# megashield_rs485.net
KiCad netlist of a schematic drawn in EAGLE
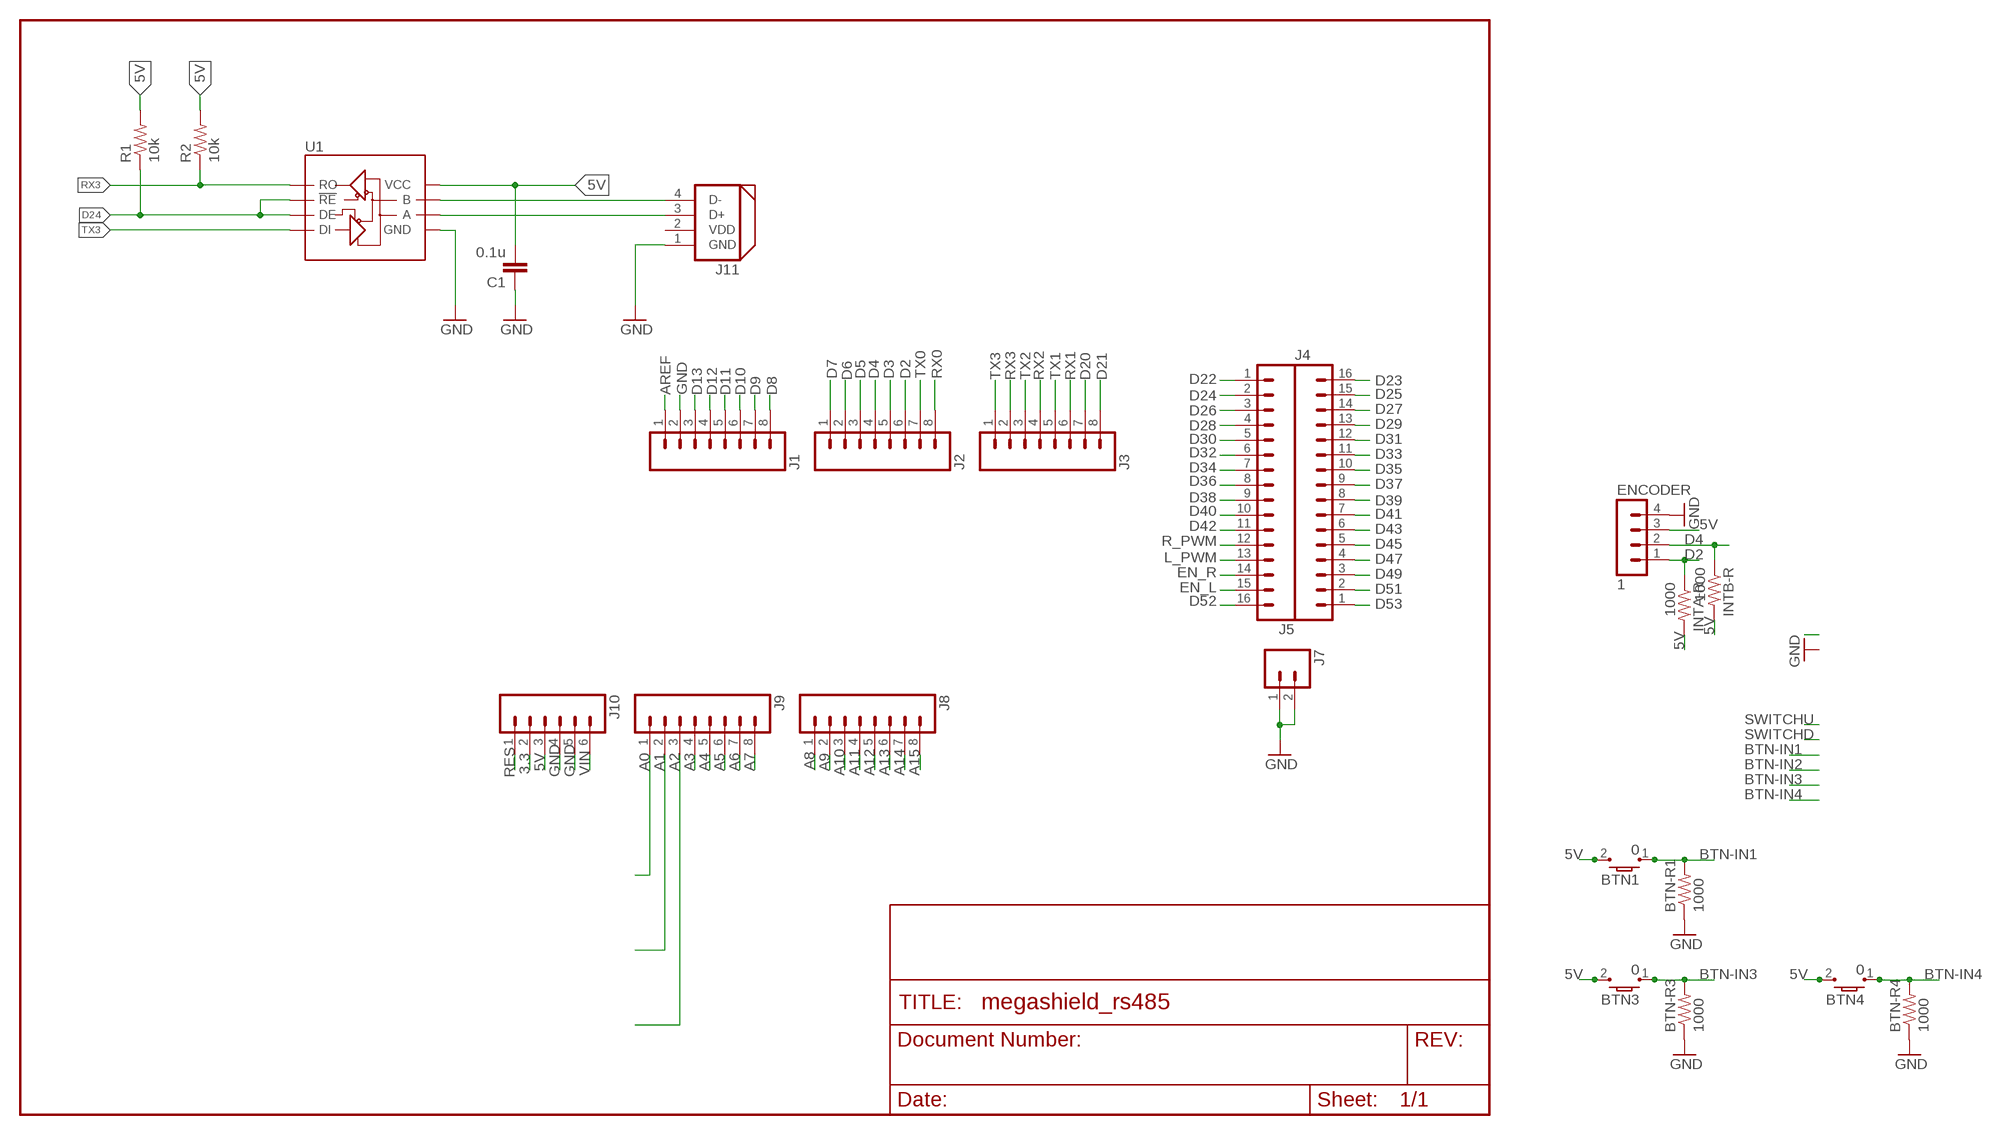
[diagram p0: schematic, sheet 1, part 1 of 2]
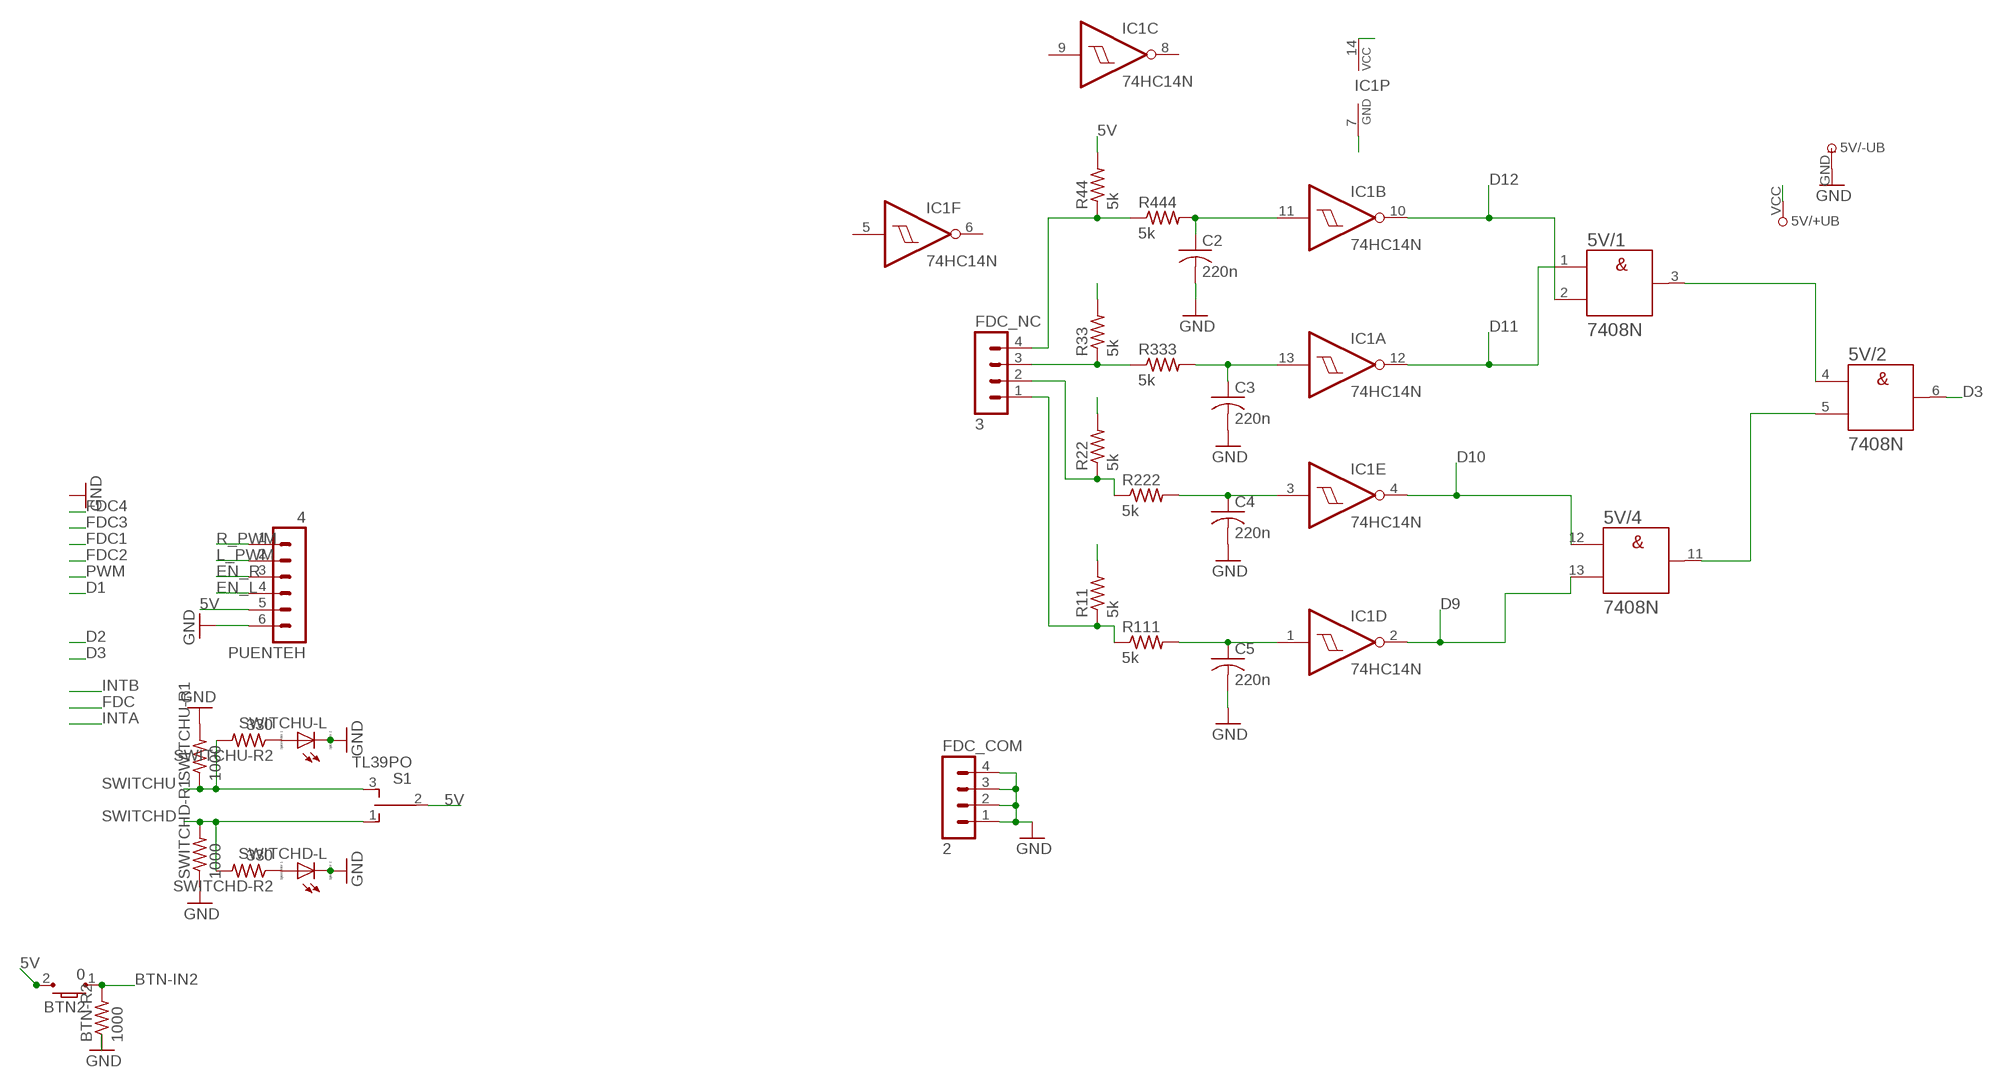
[diagram p1: schematic, sheet 1, part 2 of 2]

(export (version "E")
  (design (tool "Eeschema 10.0.6"))
  (components
    (comp (ref "5V")
      (value "7408N")
      (footprint "eagle-import:DIL14")
      (libsource (lib "eagle-import") (part "7408N"))
    )
    (comp (ref "BTN-R1")
      (value "1000")
      (footprint "eagle-import:0204_7")
      (libsource (lib "eagle-import") (part "resistor_R-US_0204/7"))
    )
    (comp (ref "BTN-R2")
      (value "1000")
      (footprint "eagle-import:0204_7")
      (libsource (lib "eagle-import") (part "resistor_R-US_0204/7"))
    )
    (comp (ref "BTN-R3")
      (value "1000")
      (footprint "eagle-import:0204_7")
      (libsource (lib "eagle-import") (part "resistor_R-US_0204/7"))
    )
    (comp (ref "BTN-R4")
      (value "1000")
      (footprint "eagle-import:0204_7")
      (libsource (lib "eagle-import") (part "resistor_R-US_0204/7"))
    )
    (comp (ref "BTN1")
      (value "0")
      (footprint "eagle-import:TL3303_J")
      (libsource (lib "eagle-import") (part "TL3302-J"))
    )
    (comp (ref "BTN2")
      (value "0")
      (footprint "eagle-import:TL3303_J")
      (libsource (lib "eagle-import") (part "TL3302-J"))
    )
    (comp (ref "BTN3")
      (value "0")
      (footprint "eagle-import:TL3303_J")
      (libsource (lib "eagle-import") (part "TL3302-J"))
    )
    (comp (ref "BTN4")
      (value "0")
      (footprint "eagle-import:TL3303_J")
      (libsource (lib "eagle-import") (part "TL3302-J"))
    )
    (comp (ref "C1")
      (value "0.1u")
      (footprint "eagle-import:CAP-PTH-SMALL")
      (libsource (lib "eagle-import") (part "CAPPTH"))
    )
    (comp (ref "C2")
      (value "220n")
      (footprint "eagle-import:C025-030X050")
      (libsource (lib "eagle-import") (part "C-US025-030X050"))
    )
    (comp (ref "C3")
      (value "220n")
      (footprint "eagle-import:C025-030X050")
      (libsource (lib "eagle-import") (part "C-US025-030X050"))
    )
    (comp (ref "C4")
      (value "220n")
      (footprint "eagle-import:C025-030X050")
      (libsource (lib "eagle-import") (part "C-US025-030X050"))
    )
    (comp (ref "C5")
      (value "220n")
      (footprint "eagle-import:C025-030X050")
      (libsource (lib "eagle-import") (part "C-US025-030X050"))
    )
    (comp (ref "ENCODER")
      (value "1")
      (footprint "eagle-import:MA04-1")
      (libsource (lib "eagle-import") (part "MA04-1"))
    )
    (comp (ref "FDC_COM")
      (value "2")
      (footprint "eagle-import:MA04-1")
      (libsource (lib "eagle-import") (part "MA04-1"))
    )
    (comp (ref "FDC_NC")
      (value "3")
      (footprint "eagle-import:MA04-1")
      (libsource (lib "eagle-import") (part "MA04-1"))
    )
    (comp (ref "IC1")
      (value "74HC14N")
      (footprint "eagle-import:DIL14")
      (libsource (lib "eagle-import") (part "7414NHC"))
    )
    (comp (ref "INTA-R")
      (value "1000")
      (footprint "eagle-import:0204_7")
      (libsource (lib "eagle-import") (part "resistor_R-US_0204/7"))
    )
    (comp (ref "INTB-R")
      (value "1000")
      (footprint "eagle-import:0204_7")
      (libsource (lib "eagle-import") (part "resistor_R-US_0204/7"))
    )
    (comp (ref "J1")
      (value "M08LONGPADS")
      (footprint "eagle-import:1X08_LONGPADS")
      (libsource (lib "eagle-import") (part "M08LONGPADS"))
    )
    (comp (ref "J2")
      (value "M08LONGPADS")
      (footprint "eagle-import:1X08_LONGPADS")
      (libsource (lib "eagle-import") (part "M08LONGPADS"))
    )
    (comp (ref "J3")
      (value "M08LONGPADS")
      (footprint "eagle-import:1X08_LONGPADS")
      (libsource (lib "eagle-import") (part "M08LONGPADS"))
    )
    (comp (ref "J4")
      (value "M16PTH")
      (footprint "eagle-import:1X16")
      (libsource (lib "eagle-import") (part "M16PTH"))
    )
    (comp (ref "J5")
      (value "M16PTH")
      (footprint "eagle-import:1X16")
      (libsource (lib "eagle-import") (part "M16PTH"))
    )
    (comp (ref "J7")
      (value "M02PTH")
      (footprint "eagle-import:1X02")
      (libsource (lib "eagle-import") (part "M02PTH"))
    )
    (comp (ref "J8")
      (value "M08LONGPADS")
      (footprint "eagle-import:1X08_LONGPADS")
      (libsource (lib "eagle-import") (part "M08LONGPADS"))
    )
    (comp (ref "J9")
      (value "M08LONGPADS")
      (footprint "eagle-import:1X08_LONGPADS")
      (libsource (lib "eagle-import") (part "M08LONGPADS"))
    )
    (comp (ref "J10")
      (value "M06LONGPADS")
      (footprint "eagle-import:1X06_LONGPADS")
      (libsource (lib "eagle-import") (part "M06LONGPADS"))
    )
    (comp (ref "J11")
      (value "DYNAMIXEL_RS485")
      (footprint "eagle-import:DYNAMIXEL_SPOX_04")
      (libsource (lib "eagle-import") (part "DYNAMIXEL_RS485"))
    )
    (comp (ref "PUENTEH")
      (value "4")
      (footprint "eagle-import:MA06-1")
      (libsource (lib "eagle-import") (part "MA06-1"))
    )
    (comp (ref "R1")
      (value "10k")
      (footprint "eagle-import:AXIAL-0.4")
      (libsource (lib "eagle-import") (part "RESISTORPTH-1/4W"))
    )
    (comp (ref "R2")
      (value "10k")
      (footprint "eagle-import:AXIAL-0.4")
      (libsource (lib "eagle-import") (part "RESISTORPTH-1/4W"))
    )
    (comp (ref "R11")
      (value "5k")
      (footprint "eagle-import:0204_7")
      (libsource (lib "eagle-import") (part "R-US_0204/7"))
    )
    (comp (ref "R22")
      (value "5k")
      (footprint "eagle-import:0204_7")
      (libsource (lib "eagle-import") (part "R-US_0204/7"))
    )
    (comp (ref "R33")
      (value "5k")
      (footprint "eagle-import:0204_7")
      (libsource (lib "eagle-import") (part "R-US_0204/7"))
    )
    (comp (ref "R44")
      (value "5k")
      (footprint "eagle-import:0204_7")
      (libsource (lib "eagle-import") (part "R-US_0204/7"))
    )
    (comp (ref "R111")
      (value "5k")
      (footprint "eagle-import:0204_7")
      (libsource (lib "eagle-import") (part "R-US_0204/7"))
    )
    (comp (ref "R222")
      (value "5k")
      (footprint "eagle-import:0204_7")
      (libsource (lib "eagle-import") (part "R-US_0204/7"))
    )
    (comp (ref "R333")
      (value "5k")
      (footprint "eagle-import:0204_7")
      (libsource (lib "eagle-import") (part "R-US_0204/7"))
    )
    (comp (ref "R444")
      (value "5k")
      (footprint "eagle-import:0204_7")
      (libsource (lib "eagle-import") (part "R-US_0204/7"))
    )
    (comp (ref "S1")
      (value "TL39PO")
      (footprint "eagle-import:TL3XPO")
      (libsource (lib "eagle-import") (part "TL39PO"))
    )
    (comp (ref "SWITCHD-L")
      (value "LED_ELD260")
      (footprint "eagle-import:LED_LD260")
      (libsource (lib "eagle-import") (part "LED_ELD260"))
    )
    (comp (ref "SWITCHD-R1")
      (value "1000")
      (footprint "eagle-import:0204_7")
      (libsource (lib "eagle-import") (part "resistor_R-US_0204/7"))
    )
    (comp (ref "SWITCHD-R2")
      (value "330")
      (footprint "eagle-import:0204_7")
      (libsource (lib "eagle-import") (part "resistor_R-US_0204/7"))
    )
    (comp (ref "SWITCHU-L")
      (value "LED_ELD260")
      (footprint "eagle-import:LED_LD260")
      (libsource (lib "eagle-import") (part "LED_ELD260"))
    )
    (comp (ref "SWITCHU-R1")
      (value "1000")
      (footprint "eagle-import:0204_7")
      (libsource (lib "eagle-import") (part "resistor_R-US_0204/7"))
    )
    (comp (ref "SWITCHU-R2")
      (value "330")
      (footprint "eagle-import:0204_7")
      (libsource (lib "eagle-import") (part "resistor_R-US_0204/7"))
    )
    (comp (ref "U1")
      (value "RS485")
      (footprint "eagle-import:DIL08")
      (libsource (lib "eagle-import") (part "SN75176B"))
    )
  )
  (nets
    (net (code "1") (name "/3.3") (class "Default")
      (node (ref "J10") (pin "2") (pinfunction "2_2") (pintype "passive"))
    )
    (net (code "2") (name "/A0") (class "Default")
      (node (ref "J9") (pin "1") (pinfunction "1_1") (pintype "passive"))
    )
    (net (code "3") (name "/A1") (class "Default")
      (node (ref "J9") (pin "2") (pinfunction "2_2") (pintype "passive"))
    )
    (net (code "4") (name "/A2") (class "Default")
      (node (ref "J9") (pin "3") (pinfunction "3_3") (pintype "passive"))
    )
    (net (code "5") (name "/A3") (class "Default")
      (node (ref "J9") (pin "4") (pinfunction "4_4") (pintype "passive"))
    )
    (net (code "6") (name "/A4") (class "Default")
      (node (ref "J9") (pin "5") (pinfunction "5_5") (pintype "passive"))
    )
    (net (code "7") (name "/A5") (class "Default")
      (node (ref "J9") (pin "6") (pinfunction "6_6") (pintype "passive"))
    )
    (net (code "8") (name "/A6") (class "Default")
      (node (ref "J9") (pin "7") (pinfunction "7_7") (pintype "passive"))
    )
    (net (code "9") (name "/A7") (class "Default")
      (node (ref "J9") (pin "8") (pinfunction "8_8") (pintype "passive"))
    )
    (net (code "10") (name "/A8") (class "Default")
      (node (ref "J8") (pin "1") (pinfunction "1_1") (pintype "passive"))
    )
    (net (code "11") (name "/A9") (class "Default")
      (node (ref "J8") (pin "2") (pinfunction "2_2") (pintype "passive"))
    )
    (net (code "12") (name "/A10") (class "Default")
      (node (ref "J8") (pin "3") (pinfunction "3_3") (pintype "passive"))
    )
    (net (code "13") (name "/A11") (class "Default")
      (node (ref "J8") (pin "4") (pinfunction "4_4") (pintype "passive"))
    )
    (net (code "14") (name "/A12") (class "Default")
      (node (ref "J8") (pin "5") (pinfunction "5_5") (pintype "passive"))
    )
    (net (code "15") (name "/A13") (class "Default")
      (node (ref "J8") (pin "6") (pinfunction "6_6") (pintype "passive"))
    )
    (net (code "16") (name "/A14") (class "Default")
      (node (ref "J8") (pin "7") (pinfunction "7_7") (pintype "passive"))
    )
    (net (code "17") (name "/A15") (class "Default")
      (node (ref "J8") (pin "8") (pinfunction "8_8") (pintype "passive"))
    )
    (net (code "18") (name "/AREF") (class "Default")
      (node (ref "J1") (pin "1") (pinfunction "1_1") (pintype "passive"))
    )
    (net (code "19") (name "/BTN-IN1") (class "Default")
      (node (ref "BTN-R1") (pin "2") (pinfunction "2_2") (pintype "passive"))
      (node (ref "BTN1") (pin "1") (pinfunction "1_1") (pintype "passive"))
    )
    (net (code "20") (name "/BTN-IN2") (class "Default")
      (node (ref "BTN-R2") (pin "2") (pinfunction "2_2") (pintype "passive"))
      (node (ref "BTN2") (pin "1") (pinfunction "1_1") (pintype "passive"))
    )
    (net (code "21") (name "/BTN-IN3") (class "Default")
      (node (ref "BTN-R3") (pin "2") (pinfunction "2_2") (pintype "passive"))
      (node (ref "BTN3") (pin "1") (pinfunction "1_1") (pintype "passive"))
    )
    (net (code "22") (name "/BTN-IN4") (class "Default")
      (node (ref "BTN-R4") (pin "2") (pinfunction "2_2") (pintype "passive"))
      (node (ref "BTN4") (pin "1") (pinfunction "1_1") (pintype "passive"))
    )
    (net (code "24") (name "/D2") (class "Default")
      (node (ref "ENCODER") (pin "1") (pinfunction "1_1") (pintype "passive"))
      (node (ref "INTA-R") (pin "1") (pinfunction "1_1") (pintype "passive"))
      (node (ref "J2") (pin "6") (pinfunction "6_6") (pintype "passive"))
    )
    (net (code "25") (name "/D3") (class "Default")
      (node (ref "5V") (pin "6") (pinfunction "Y_6") (pintype "output"))
      (node (ref "J2") (pin "5") (pinfunction "5_5") (pintype "passive"))
    )
    (net (code "26") (name "/D4") (class "Default")
      (node (ref "ENCODER") (pin "2") (pinfunction "2_2") (pintype "passive"))
      (node (ref "INTB-R") (pin "1") (pinfunction "1_1") (pintype "passive"))
      (node (ref "J2") (pin "4") (pinfunction "4_4") (pintype "passive"))
    )
    (net (code "27") (name "/D5") (class "Default")
      (node (ref "J2") (pin "3") (pinfunction "3_3") (pintype "passive"))
    )
    (net (code "28") (name "/D6") (class "Default")
      (node (ref "J2") (pin "2") (pinfunction "2_2") (pintype "passive"))
    )
    (net (code "29") (name "/D7") (class "Default")
      (node (ref "J2") (pin "1") (pinfunction "1_1") (pintype "passive"))
    )
    (net (code "30") (name "/D8") (class "Default")
      (node (ref "J1") (pin "8") (pinfunction "8_8") (pintype "passive"))
    )
    (net (code "31") (name "/D9") (class "Default")
      (node (ref "5V") (pin "13") (pinfunction "B_13") (pintype "input"))
      (node (ref "IC1") (pin "2") (pinfunction "O_2") (pintype "output"))
      (node (ref "J1") (pin "7") (pinfunction "7_7") (pintype "passive"))
    )
    (net (code "32") (name "/D10") (class "Default")
      (node (ref "5V") (pin "12") (pinfunction "A_12") (pintype "input"))
      (node (ref "IC1") (pin "4") (pinfunction "O_4") (pintype "output"))
      (node (ref "J1") (pin "6") (pinfunction "6_6") (pintype "passive"))
    )
    (net (code "33") (name "/D11") (class "Default")
      (node (ref "5V") (pin "1") (pinfunction "A_1") (pintype "input"))
      (node (ref "IC1") (pin "12") (pinfunction "O_12") (pintype "output"))
      (node (ref "J1") (pin "5") (pinfunction "5_5") (pintype "passive"))
    )
    (net (code "34") (name "/D12") (class "Default")
      (node (ref "5V") (pin "2") (pinfunction "B_2") (pintype "input"))
      (node (ref "IC1") (pin "10") (pinfunction "O_10") (pintype "output"))
      (node (ref "J1") (pin "4") (pinfunction "4_4") (pintype "passive"))
    )
    (net (code "35") (name "/D13") (class "Default")
      (node (ref "J1") (pin "3") (pinfunction "3_3") (pintype "passive"))
    )
    (net (code "36") (name "/D20") (class "Default")
      (node (ref "J3") (pin "7") (pinfunction "7_7") (pintype "passive"))
    )
    (net (code "37") (name "/D21") (class "Default")
      (node (ref "J3") (pin "8") (pinfunction "8_8") (pintype "passive"))
    )
    (net (code "38") (name "/D22") (class "Default")
      (node (ref "J5") (pin "1") (pinfunction "1_1") (pintype "passive"))
    )
    (net (code "39") (name "/D23") (class "Default")
      (node (ref "J4") (pin "16") (pinfunction "16_16") (pintype "passive"))
    )
    (net (code "40") (name "/D25") (class "Default")
      (node (ref "J4") (pin "15") (pinfunction "15_15") (pintype "passive"))
    )
    (net (code "41") (name "/D26") (class "Default")
      (node (ref "J5") (pin "3") (pinfunction "3_3") (pintype "passive"))
    )
    (net (code "42") (name "/D27") (class "Default")
      (node (ref "J4") (pin "14") (pinfunction "14_14") (pintype "passive"))
    )
    (net (code "43") (name "/D28") (class "Default")
      (node (ref "J5") (pin "4") (pinfunction "4_4") (pintype "passive"))
    )
    (net (code "44") (name "/D29") (class "Default")
      (node (ref "J4") (pin "13") (pinfunction "13_13") (pintype "passive"))
    )
    (net (code "45") (name "/D30") (class "Default")
      (node (ref "J5") (pin "5") (pinfunction "5_5") (pintype "passive"))
    )
    (net (code "46") (name "/D31") (class "Default")
      (node (ref "J4") (pin "12") (pinfunction "12_12") (pintype "passive"))
    )
    (net (code "47") (name "/D32") (class "Default")
      (node (ref "J5") (pin "6") (pinfunction "6_6") (pintype "passive"))
    )
    (net (code "48") (name "/D33") (class "Default")
      (node (ref "J4") (pin "11") (pinfunction "11_11") (pintype "passive"))
    )
    (net (code "49") (name "/D34") (class "Default")
      (node (ref "J5") (pin "7") (pinfunction "7_7") (pintype "passive"))
    )
    (net (code "50") (name "/D35") (class "Default")
      (node (ref "J4") (pin "10") (pinfunction "10_10") (pintype "passive"))
    )
    (net (code "51") (name "/D36") (class "Default")
      (node (ref "J5") (pin "8") (pinfunction "8_8") (pintype "passive"))
    )
    (net (code "52") (name "/D37") (class "Default")
      (node (ref "J4") (pin "9") (pinfunction "9_9") (pintype "passive"))
    )
    (net (code "53") (name "/D38") (class "Default")
      (node (ref "J5") (pin "9") (pinfunction "9_9") (pintype "passive"))
    )
    (net (code "54") (name "/D39") (class "Default")
      (node (ref "J4") (pin "8") (pinfunction "8_8") (pintype "passive"))
    )
    (net (code "55") (name "/D40") (class "Default")
      (node (ref "J5") (pin "10") (pinfunction "10_10") (pintype "passive"))
    )
    (net (code "56") (name "/D41") (class "Default")
      (node (ref "J4") (pin "7") (pinfunction "7_7") (pintype "passive"))
    )
    (net (code "57") (name "/D42") (class "Default")
      (node (ref "J5") (pin "11") (pinfunction "11_11") (pintype "passive"))
    )
    (net (code "58") (name "/D43") (class "Default")
      (node (ref "J4") (pin "6") (pinfunction "6_6") (pintype "passive"))
    )
    (net (code "59") (name "/D45") (class "Default")
      (node (ref "J4") (pin "5") (pinfunction "5_5") (pintype "passive"))
    )
    (net (code "60") (name "/D47") (class "Default")
      (node (ref "J4") (pin "4") (pinfunction "4_4") (pintype "passive"))
    )
    (net (code "61") (name "/D49") (class "Default")
      (node (ref "J4") (pin "3") (pinfunction "3_3") (pintype "passive"))
    )
    (net (code "62") (name "/D51") (class "Default")
      (node (ref "J4") (pin "2") (pinfunction "2_2") (pintype "passive"))
    )
    (net (code "63") (name "/D52") (class "Default")
      (node (ref "J5") (pin "16") (pinfunction "16_16") (pintype "passive"))
    )
    (net (code "64") (name "/D53") (class "Default")
      (node (ref "J4") (pin "1") (pinfunction "1_1") (pintype "passive"))
    )
    (net (code "65") (name "/EN_L") (class "Default")
      (node (ref "J5") (pin "15") (pinfunction "15_15") (pintype "passive"))
      (node (ref "PUENTEH") (pin "4") (pinfunction "4_4") (pintype "passive"))
    )
    (net (code "66") (name "/EN_R") (class "Default")
      (node (ref "J5") (pin "14") (pinfunction "14_14") (pintype "passive"))
      (node (ref "PUENTEH") (pin "3") (pinfunction "3_3") (pintype "passive"))
    )
    (net (code "74") (name "/L_PWM") (class "Default")
      (node (ref "J5") (pin "13") (pinfunction "13_13") (pintype "passive"))
      (node (ref "PUENTEH") (pin "2") (pinfunction "2_2") (pintype "passive"))
    )
    (net (code "76") (name "/RES") (class "Default")
      (node (ref "J10") (pin "1") (pinfunction "1_1") (pintype "passive"))
    )
    (net (code "77") (name "/RX0") (class "Default")
      (node (ref "J2") (pin "8") (pinfunction "8_8") (pintype "passive"))
    )
    (net (code "78") (name "/RX1") (class "Default")
      (node (ref "J3") (pin "6") (pinfunction "6_6") (pintype "passive"))
    )
    (net (code "79") (name "/RX2") (class "Default")
      (node (ref "J3") (pin "4") (pinfunction "4_4") (pintype "passive"))
    )
    (net (code "80") (name "/R_PWM") (class "Default")
      (node (ref "J5") (pin "12") (pinfunction "12_12") (pintype "passive"))
      (node (ref "PUENTEH") (pin "1") (pinfunction "1_1") (pintype "passive"))
    )
    (net (code "81") (name "/SWITCHD") (class "Default")
      (node (ref "S1") (pin "1") (pinfunction "O_1") (pintype "passive"))
      (node (ref "SWITCHD-R1") (pin "2") (pinfunction "2_2") (pintype "passive"))
      (node (ref "SWITCHD-R2") (pin "2") (pinfunction "2_2") (pintype "passive"))
    )
    (net (code "82") (name "/SWITCHU") (class "Default")
      (node (ref "S1") (pin "3") (pinfunction "S_3") (pintype "passive"))
      (node (ref "SWITCHU-R1") (pin "1") (pinfunction "1_1") (pintype "passive"))
      (node (ref "SWITCHU-R2") (pin "2") (pinfunction "2_2") (pintype "passive"))
    )
    (net (code "83") (name "/TX0") (class "Default")
      (node (ref "J2") (pin "7") (pinfunction "7_7") (pintype "passive"))
    )
    (net (code "84") (name "/TX1") (class "Default")
      (node (ref "J3") (pin "5") (pinfunction "5_5") (pintype "passive"))
    )
    (net (code "85") (name "/TX2") (class "Default")
      (node (ref "J3") (pin "3") (pinfunction "3_3") (pintype "passive"))
    )
    (net (code "86") (name "/VDD") (class "Default")
      (node (ref "J11") (pin "2") (pinfunction "VDD_2") (pintype "power_in"))
    )
    (net (code "87") (name "/VIN") (class "Default")
      (node (ref "J10") (pin "6") (pinfunction "6_6") (pintype "passive"))
    )
    (net (code "88") (name "5V") (class "Default")
      (node (ref "5V") (pin "VCC") (pinfunction "+UB_VCC") (pintype "power_in"))
      (node (ref "BTN1") (pin "2") (pinfunction "2_2") (pintype "passive"))
      (node (ref "BTN2") (pin "2") (pinfunction "2_2") (pintype "passive"))
      (node (ref "BTN3") (pin "2") (pinfunction "2_2") (pintype "passive"))
      (node (ref "BTN4") (pin "2") (pinfunction "2_2") (pintype "passive"))
      (node (ref "C1") (pin "2") (pinfunction "2_2") (pintype "passive"))
      (node (ref "ENCODER") (pin "3") (pinfunction "3_3") (pintype "passive"))
      (node (ref "IC1") (pin "14") (pinfunction "VCC_14") (pintype "power_in"))
      (node (ref "INTA-R") (pin "2") (pinfunction "2_2") (pintype "passive"))
      (node (ref "INTB-R") (pin "2") (pinfunction "2_2") (pintype "passive"))
      (node (ref "J10") (pin "3") (pinfunction "3_3") (pintype "passive"))
      (node (ref "PUENTEH") (pin "5") (pinfunction "5_5") (pintype "passive"))
      (node (ref "R1") (pin "P$2") (pinfunction "2_P$2") (pintype "passive"))
      (node (ref "R11") (pin "2") (pinfunction "2_2") (pintype "passive"))
      (node (ref "R2") (pin "P$2") (pinfunction "2_P$2") (pintype "passive"))
      (node (ref "R22") (pin "2") (pinfunction "2_2") (pintype "passive"))
      (node (ref "R33") (pin "2") (pinfunction "2_2") (pintype "passive"))
      (node (ref "R44") (pin "2") (pinfunction "2_2") (pintype "passive"))
      (node (ref "S1") (pin "2") (pinfunction "P_2") (pintype "passive"))
      (node (ref "U1") (pin "8") (pinfunction "VCC_8") (pintype "bidirectional"))
    )
    (net (code "89") (name "D24") (class "Default")
      (node (ref "J5") (pin "2") (pinfunction "2_2") (pintype "passive"))
      (node (ref "R1") (pin "P$1") (pinfunction "1_P$1") (pintype "passive"))
      (node (ref "U1") (pin "2") (pinfunction "~{RE}_2") (pintype "bidirectional"))
      (node (ref "U1") (pin "3") (pinfunction "DE_3") (pintype "bidirectional"))
    )
    (net (code "90") (name "GND") (class "Default")
      (node (ref "5V") (pin "GND") (pinfunction "-UB_GND") (pintype "power_in"))
      (node (ref "BTN-R1") (pin "1") (pinfunction "1_1") (pintype "passive"))
      (node (ref "BTN-R2") (pin "1") (pinfunction "1_1") (pintype "passive"))
      (node (ref "BTN-R3") (pin "1") (pinfunction "1_1") (pintype "passive"))
      (node (ref "BTN-R4") (pin "1") (pinfunction "1_1") (pintype "passive"))
      (node (ref "C1") (pin "1") (pinfunction "1_1") (pintype "passive"))
      (node (ref "C2") (pin "2") (pinfunction "2_2") (pintype "passive"))
      (node (ref "C3") (pin "2") (pinfunction "2_2") (pintype "passive"))
      (node (ref "C4") (pin "2") (pinfunction "2_2") (pintype "passive"))
      (node (ref "C5") (pin "2") (pinfunction "2_2") (pintype "passive"))
      (node (ref "ENCODER") (pin "4") (pinfunction "4_4") (pintype "passive"))
      (node (ref "FDC_COM") (pin "1") (pinfunction "1_1") (pintype "passive"))
      (node (ref "FDC_COM") (pin "2") (pinfunction "2_2") (pintype "passive"))
      (node (ref "FDC_COM") (pin "3") (pinfunction "3_3") (pintype "passive"))
      (node (ref "FDC_COM") (pin "4") (pinfunction "4_4") (pintype "passive"))
      (node (ref "IC1") (pin "7") (pinfunction "GND_7") (pintype "power_in"))
      (node (ref "J1") (pin "2") (pinfunction "2_2") (pintype "passive"))
      (node (ref "J10") (pin "4") (pinfunction "4_4") (pintype "passive"))
      (node (ref "J10") (pin "5") (pinfunction "5_5") (pintype "passive"))
      (node (ref "J11") (pin "1") (pinfunction "GND_1") (pintype "power_in"))
      (node (ref "J7") (pin "1") (pinfunction "1_1") (pintype "passive"))
      (node (ref "J7") (pin "2") (pinfunction "2_2") (pintype "passive"))
      (node (ref "PUENTEH") (pin "6") (pinfunction "6_6") (pintype "passive"))
      (node (ref "SWITCHD-L") (pin "K") (pinfunction "C_K") (pintype "passive"))
      (node (ref "SWITCHD-R1") (pin "1") (pinfunction "1_1") (pintype "passive"))
      (node (ref "SWITCHU-L") (pin "K") (pinfunction "C_K") (pintype "passive"))
      (node (ref "SWITCHU-R1") (pin "2") (pinfunction "2_2") (pintype "passive"))
      (node (ref "U1") (pin "5") (pinfunction "GND_5") (pintype "bidirectional"))
    )
    (net (code "91") (name "Net-(5VC-Y)") (class "Default")
      (node (ref "5V") (pin "3") (pinfunction "Y_3") (pintype "output"))
      (node (ref "5V") (pin "4") (pinfunction "A_4") (pintype "input"))
    )
    (net (code "92") (name "Net-(5VD-B)") (class "Default")
      (node (ref "5V") (pin "11") (pinfunction "Y_11") (pintype "output"))
      (node (ref "5V") (pin "5") (pinfunction "B_5") (pintype "input"))
    )
    (net (code "93") (name "Net-(FDC_NC-Pad1)") (class "Default")
      (node (ref "FDC_NC") (pin "1") (pinfunction "1_1") (pintype "passive"))
      (node (ref "R11") (pin "1") (pinfunction "1_1") (pintype "passive"))
      (node (ref "R111") (pin "1") (pinfunction "1_1") (pintype "passive"))
    )
    (net (code "94") (name "Net-(FDC_NC-Pad2)") (class "Default")
      (node (ref "FDC_NC") (pin "2") (pinfunction "2_2") (pintype "passive"))
      (node (ref "R22") (pin "1") (pinfunction "1_1") (pintype "passive"))
      (node (ref "R222") (pin "1") (pinfunction "1_1") (pintype "passive"))
    )
    (net (code "95") (name "Net-(FDC_NC-Pad3)") (class "Default")
      (node (ref "FDC_NC") (pin "3") (pinfunction "3_3") (pintype "passive"))
      (node (ref "R33") (pin "1") (pinfunction "1_1") (pintype "passive"))
      (node (ref "R333") (pin "1") (pinfunction "1_1") (pintype "passive"))
    )
    (net (code "96") (name "Net-(FDC_NC-Pad4)") (class "Default")
      (node (ref "FDC_NC") (pin "4") (pinfunction "4_4") (pintype "passive"))
      (node (ref "R44") (pin "1") (pinfunction "1_1") (pintype "passive"))
      (node (ref "R444") (pin "1") (pinfunction "1_1") (pintype "passive"))
    )
    (net (code "97") (name "Net-(IC1A-I)") (class "Default")
      (node (ref "C3") (pin "1") (pinfunction "1_1") (pintype "passive"))
      (node (ref "IC1") (pin "13") (pinfunction "I_13") (pintype "input"))
      (node (ref "R333") (pin "2") (pinfunction "2_2") (pintype "passive"))
    )
    (net (code "98") (name "Net-(IC1B-I)") (class "Default")
      (node (ref "C2") (pin "1") (pinfunction "1_1") (pintype "passive"))
      (node (ref "IC1") (pin "11") (pinfunction "I_11") (pintype "input"))
      (node (ref "R444") (pin "2") (pinfunction "2_2") (pintype "passive"))
    )
    (net (code "99") (name "Net-(IC1D-I)") (class "Default")
      (node (ref "C5") (pin "1") (pinfunction "1_1") (pintype "passive"))
      (node (ref "IC1") (pin "1") (pinfunction "I_1") (pintype "input"))
      (node (ref "R111") (pin "2") (pinfunction "2_2") (pintype "passive"))
    )
    (net (code "100") (name "Net-(IC1E-I)") (class "Default")
      (node (ref "C4") (pin "1") (pinfunction "1_1") (pintype "passive"))
      (node (ref "IC1") (pin "3") (pinfunction "I_3") (pintype "input"))
      (node (ref "R222") (pin "2") (pinfunction "2_2") (pintype "passive"))
    )
    (net (code "101") (name "Net-(J11-D+)") (class "Default")
      (node (ref "J11") (pin "3") (pinfunction "D+_3") (pintype "bidirectional"))
      (node (ref "U1") (pin "6") (pinfunction "A_6") (pintype "bidirectional"))
    )
    (net (code "102") (name "Net-(J11-D-)") (class "Default")
      (node (ref "J11") (pin "4") (pinfunction "D-_4") (pintype "bidirectional"))
      (node (ref "U1") (pin "7") (pinfunction "B_7") (pintype "bidirectional"))
    )
    (net (code "103") (name "Net-(SWITCHD-L-PadA)") (class "Default")
      (node (ref "SWITCHD-L") (pin "A") (pinfunction "A_A") (pintype "passive"))
      (node (ref "SWITCHD-R2") (pin "1") (pinfunction "1_1") (pintype "passive"))
    )
    (net (code "104") (name "Net-(SWITCHU-L-PadA)") (class "Default")
      (node (ref "SWITCHU-L") (pin "A") (pinfunction "A_A") (pintype "passive"))
      (node (ref "SWITCHU-R2") (pin "1") (pinfunction "1_1") (pintype "passive"))
    )
    (net (code "105") (name "RX3") (class "Default")
      (node (ref "J3") (pin "2") (pinfunction "2_2") (pintype "passive"))
      (node (ref "R2") (pin "P$1") (pinfunction "1_P$1") (pintype "passive"))
      (node (ref "U1") (pin "1") (pinfunction "RO_1") (pintype "bidirectional"))
    )
    (net (code "106") (name "TX3") (class "Default")
      (node (ref "J3") (pin "1") (pinfunction "1_1") (pintype "passive"))
      (node (ref "U1") (pin "4") (pinfunction "DI_4") (pintype "bidirectional"))
    )
    (net (code "107") (name "unconnected-(IC1C-I-Pad9)") (class "Default")
      (node (ref "IC1") (pin "9") (pinfunction "I_9") (pintype "input"))
    )
    (net (code "108") (name "unconnected-(IC1C-O-Pad8)") (class "Default")
      (node (ref "IC1") (pin "8") (pinfunction "O_8") (pintype "output"))
    )
    (net (code "109") (name "unconnected-(IC1F-I-Pad5)") (class "Default")
      (node (ref "IC1") (pin "5") (pinfunction "I_5") (pintype "input"))
    )
    (net (code "110") (name "unconnected-(IC1F-O-Pad6)") (class "Default")
      (node (ref "IC1") (pin "6") (pinfunction "O_6") (pintype "output"))
    )
  )
)
